# LEDs.net
KiCad netlist of a schematic drawn in Altium Designer
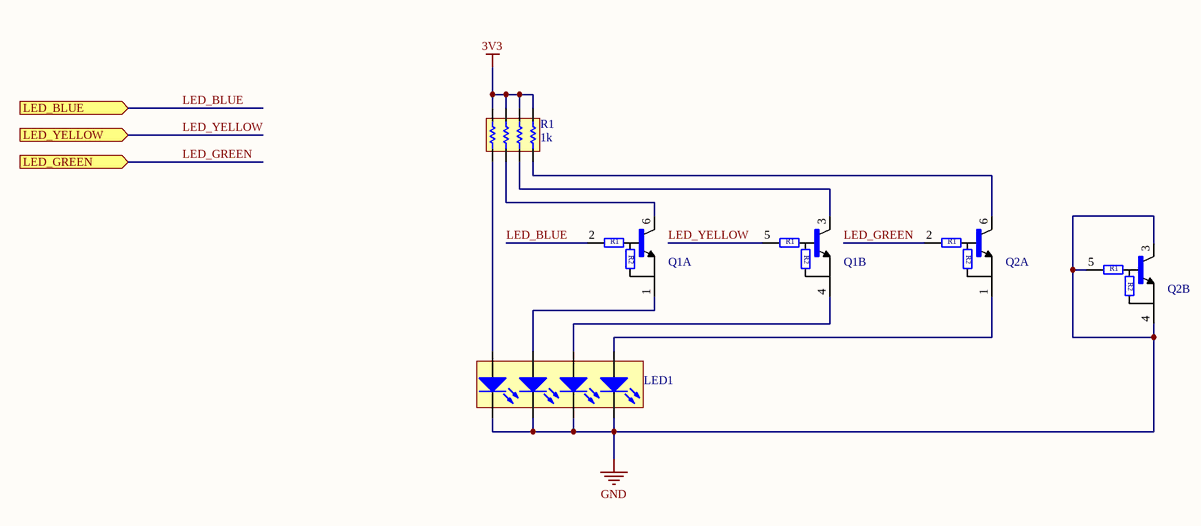
[diagram p0: LEDs.SchDoc]

(export (version "E")
  (design (tool "Eeschema 10.0.6"))
  (components
    (comp (ref "LED1")
      (value "LED 4x")
      (footprint "MENTOR 1296.2022")
      (fields (field (name "MANUFACTURER") "Lucky Light") (field (name "MPN") "LL-S194PUAC-2A"))
      (libsource (lib "agh_racing_2018") (part "LED 4x"))
    )
    (comp (ref "Q1")
      (value "NPN BRT BCR116")
      (footprint "SOT363_IPC_MD")
      (description "NPN Transistors pair with built-in bias resistor, R1 = 4k7, R2 = 47k")
      (libsource (lib "agh_racing_2018") (part "BCR116"))
    )
    (comp (ref "Q2")
      (value "NPN BRT BCR116")
      (footprint "SOT363_IPC_MD")
      (description "NPN Transistors pair with built-in bias resistor, R1 = 4k7, R2 = 47k")
      (libsource (lib "agh_racing_2018") (part "BCR116"))
    )
    (comp (ref "R1")
      (value "1k")
      (footprint "RES_ARR_1206_IPC_LD")
      (description "Array Chip Resistors")
      (fields (field (name "Comment") "Res"))
      (libsource (lib "agh_racing_2018") (part "Res Array"))
    )
  )
  (nets
    (net (code "1") (name "/LED_BLUE") (class "Default")
      (node (ref "Q1") (pin "2") (pinfunction "B1_2") (pintype "passive"))
    )
    (net (code "2") (name "/LED_GREEN") (class "Default")
      (node (ref "Q2") (pin "2") (pinfunction "B1_2") (pintype "passive"))
    )
    (net (code "3") (name "/LED_YELLOW") (class "Default")
      (node (ref "Q1") (pin "5") (pinfunction "B2_5") (pintype "passive"))
    )
    (net (code "4") (name "3V3") (class "Default")
      (node (ref "R1") (pin "1") (pinfunction "1_1") (pintype "passive"))
      (node (ref "R1") (pin "2") (pinfunction "2_2") (pintype "passive"))
      (node (ref "R1") (pin "3") (pinfunction "3_3") (pintype "passive"))
      (node (ref "R1") (pin "4") (pinfunction "4_4") (pintype "passive"))
    )
    (net (code "5") (name "GND") (class "Default")
      (node (ref "LED1") (pin "2") (pinfunction "K1_2") (pintype "passive"))
      (node (ref "LED1") (pin "4") (pinfunction "K2_4") (pintype "passive"))
      (node (ref "LED1") (pin "6") (pinfunction "K3_6") (pintype "passive"))
      (node (ref "LED1") (pin "8") (pinfunction "K4_8") (pintype "passive"))
      (node (ref "Q2") (pin "3") (pinfunction "C2_3") (pintype "passive"))
      (node (ref "Q2") (pin "4") (pinfunction "E2_4") (pintype "passive"))
      (node (ref "Q2") (pin "5") (pinfunction "B2_5") (pintype "passive"))
    )
    (net (code "6") (name "Net-(LED1-A1)") (class "Default")
      (node (ref "LED1") (pin "1") (pinfunction "A1_1") (pintype "passive"))
      (node (ref "R1") (pin "8") (pinfunction "8_8") (pintype "passive"))
    )
    (net (code "7") (name "Net-(LED1-A2)") (class "Default")
      (node (ref "LED1") (pin "3") (pinfunction "A2_3") (pintype "passive"))
      (node (ref "Q1") (pin "1") (pinfunction "E1_1") (pintype "passive"))
    )
    (net (code "8") (name "Net-(LED1-A3)") (class "Default")
      (node (ref "LED1") (pin "5") (pinfunction "A3_5") (pintype "passive"))
      (node (ref "Q1") (pin "4") (pinfunction "E2_4") (pintype "passive"))
    )
    (net (code "9") (name "Net-(LED1-A4)") (class "Default")
      (node (ref "LED1") (pin "7") (pinfunction "A4_7") (pintype "passive"))
      (node (ref "Q2") (pin "1") (pinfunction "E1_1") (pintype "passive"))
    )
    (net (code "10") (name "Net-(Q1A-C1)") (class "Default")
      (node (ref "Q1") (pin "6") (pinfunction "C1_6") (pintype "passive"))
      (node (ref "R1") (pin "7") (pinfunction "7_7") (pintype "passive"))
    )
    (net (code "11") (name "Net-(Q1B-C2)") (class "Default")
      (node (ref "Q1") (pin "3") (pinfunction "C2_3") (pintype "passive"))
      (node (ref "R1") (pin "6") (pinfunction "6_6") (pintype "passive"))
    )
    (net (code "12") (name "Net-(Q2A-C1)") (class "Default")
      (node (ref "Q2") (pin "6") (pinfunction "C1_6") (pintype "passive"))
      (node (ref "R1") (pin "5") (pinfunction "5_5") (pintype "passive"))
    )
  )
)
